# M2male_M2female_miniDP.net
KiCad netlist of a schematic drawn in Altium Designer
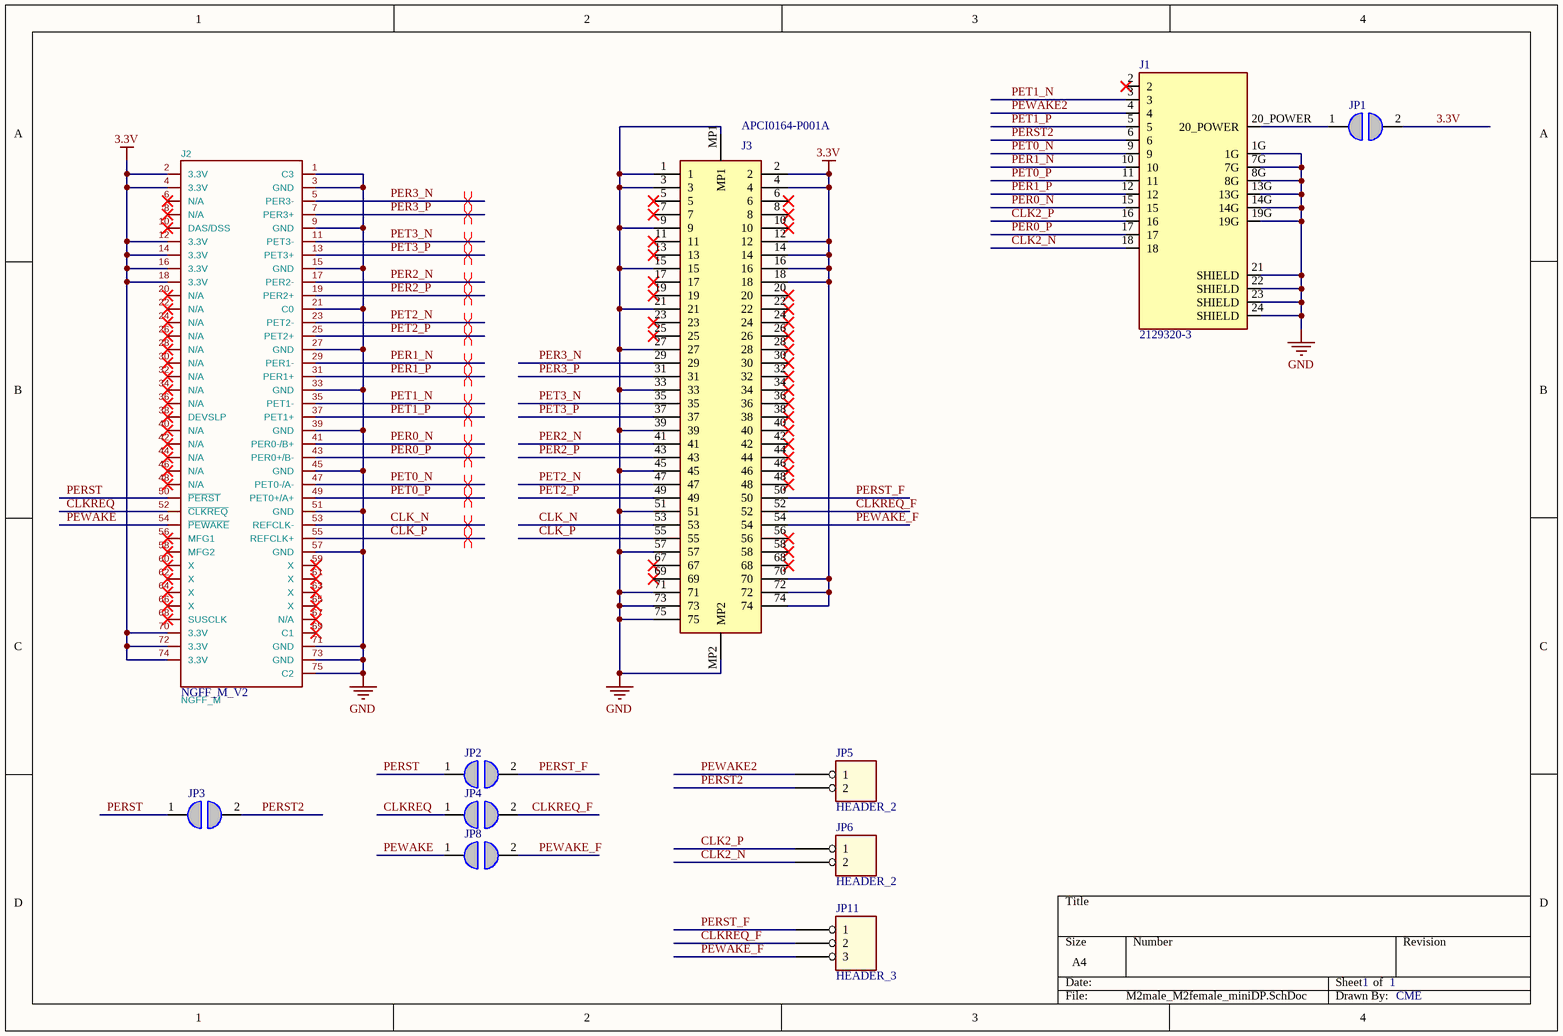
[diagram p0: M2male_M2female_miniDP.SchDoc]

(export (version "E")
  (design (tool "Eeschema 10.0.6"))
  (components
    (comp (ref "J1")
      (value "2129320-3")
      (footprint "CME_LIB:CONN_2129320-3")
      (description "Conn Display Port RCP 20 POS 0.9mm/1.8mm Solder RA Thru-Hole 20 Terminal 1 Port T/R")
      (fields (field (name "DIGI-KEY_PART_NUMBER") "A120537CT-ND") (field (name "MF") "TE Connectivity"))
      (libsource (lib "CME_LIB") (part "2129320-3"))
    )
    (comp (ref "J2")
      (value "NGFF_M_V2")
      (footprint "M2male_M2female_miniDP:M.2-M-KEY-2280-V2")
      (fields (field (name "ALTIUM_VALUE") "NGFF_M"))
      (libsource (lib "M2male_M2female_miniDP") (part "NGFF_M_V2"))
    )
    (comp (ref "J3")
      (value "APCI0164-P001A")
      (footprint "CME_LIB:APCI0164P001A")
      (description "Connector")
      (libsource (lib "*") (part "APCI0164-P001A"))
    )
    (comp (ref "JP1")
      (value "JUMPER_A_SOUDER")
      (footprint "JUMPER_A_SOUDER (0201)")
      (description "Pont à souder sur print")
      (libsource (lib "DatabaseReDS") (part "JUMPER_A_SOUDER"))
    )
    (comp (ref "JP2")
      (value "JUMPER_A_SOUDER")
      (footprint "JUMPER_A_SOUDER (0201)")
      (description "Pont à souder sur print")
      (libsource (lib "DatabaseReDS") (part "JUMPER_A_SOUDER"))
    )
    (comp (ref "JP3")
      (value "JUMPER_A_SOUDER")
      (footprint "JUMPER_A_SOUDER (0201)")
      (description "Pont à souder sur print")
      (libsource (lib "DatabaseReDS") (part "JUMPER_A_SOUDER"))
    )
    (comp (ref "JP4")
      (value "JUMPER_A_SOUDER")
      (footprint "JUMPER_A_SOUDER (0201)")
      (description "Pont à souder sur print")
      (libsource (lib "DatabaseReDS") (part "JUMPER_A_SOUDER"))
    )
    (comp (ref "JP5")
      (value "HEADER_2")
      (footprint "BLKCON.100/VH/TM1SQ/W.100/2")
      (description "Barrette simple 2 poles 2.54mm")
      (fields (field (name "MANUFACTURER") "TE Connectivity"))
      (libsource (lib "DatabaseReDS") (part "HEADER_2"))
    )
    (comp (ref "JP6")
      (value "HEADER_2")
      (footprint "BLKCON.100/VH/TM1SQ/W.100/2")
      (description "Barrette simple 2 poles 2.54mm")
      (fields (field (name "MANUFACTURER") "TE Connectivity"))
      (libsource (lib "DatabaseReDS") (part "HEADER_2"))
    )
    (comp (ref "JP8")
      (value "JUMPER_A_SOUDER")
      (footprint "JUMPER_A_SOUDER (0201)")
      (description "Pont à souder sur print")
      (libsource (lib "DatabaseReDS") (part "JUMPER_A_SOUDER"))
    )
    (comp (ref "JP11")
      (value "HEADER_3")
      (footprint "BLKCON.100/VH/TM1SQ/W.100/3")
      (description "Barrette simple 3 poles 2.54mm")
      (fields (field (name "MANUFACTURER") "TE Connectivity"))
      (libsource (lib "DatabaseReDS") (part "HEADER_3"))
    )
  )
  (nets
    (net (code "1") (name "/CLK2_N") (class "Default")
      (node (ref "J1") (pin "18") (pinfunction "18_18") (pintype "passive"))
      (node (ref "JP6") (pin "2") (pinfunction "2_2") (pintype "passive"))
    )
    (net (code "2") (name "/CLK2_P") (class "Default")
      (node (ref "J1") (pin "16") (pinfunction "16_16") (pintype "passive"))
      (node (ref "JP6") (pin "1") (pinfunction "1_1") (pintype "passive"))
    )
    (net (code "3") (name "/CLKREQ") (class "Default")
      (node (ref "J2") (pin "52") (pinfunction "~{CLKREQ}_52") (pintype "passive"))
      (node (ref "JP4") (pin "1") (pinfunction "1_1") (pintype "passive"))
    )
    (net (code "4") (name "/CLKREQ_F") (class "Default")
      (node (ref "J3") (pin "52") (pinfunction "52_52") (pintype "passive"))
      (node (ref "JP11") (pin "2") (pinfunction "2_2") (pintype "passive"))
      (node (ref "JP4") (pin "2") (pinfunction "2_2") (pintype "passive"))
    )
    (net (code "5") (name "/CLK_N") (class "Default")
      (node (ref "J2") (pin "53") (pinfunction "REFCLK-_53") (pintype "passive"))
      (node (ref "J3") (pin "53") (pinfunction "53_53") (pintype "passive"))
    )
    (net (code "6") (name "/CLK_P") (class "Default")
      (node (ref "J2") (pin "55") (pinfunction "REFCLK+_55") (pintype "passive"))
      (node (ref "J3") (pin "55") (pinfunction "55_55") (pintype "passive"))
    )
    (net (code "7") (name "/PER0_N") (class "Default")
      (node (ref "J1") (pin "15") (pinfunction "15_15") (pintype "passive"))
      (node (ref "J2") (pin "41") (pinfunction "PER0-/B+_41") (pintype "passive"))
    )
    (net (code "8") (name "/PER0_P") (class "Default")
      (node (ref "J1") (pin "17") (pinfunction "17_17") (pintype "passive"))
      (node (ref "J2") (pin "43") (pinfunction "PER0+/B-_43") (pintype "passive"))
    )
    (net (code "9") (name "/PER1_N") (class "Default")
      (node (ref "J1") (pin "10") (pinfunction "10_10") (pintype "passive"))
      (node (ref "J2") (pin "29") (pinfunction "PER1-_29") (pintype "passive"))
    )
    (net (code "10") (name "/PER1_P") (class "Default")
      (node (ref "J1") (pin "12") (pinfunction "12_12") (pintype "passive"))
      (node (ref "J2") (pin "31") (pinfunction "PER1+_31") (pintype "passive"))
    )
    (net (code "11") (name "/PER2_N") (class "Default")
      (node (ref "J2") (pin "17") (pinfunction "PER2-_17") (pintype "passive"))
      (node (ref "J3") (pin "41") (pinfunction "41_41") (pintype "passive"))
    )
    (net (code "12") (name "/PER2_P") (class "Default")
      (node (ref "J2") (pin "19") (pinfunction "PER2+_19") (pintype "passive"))
      (node (ref "J3") (pin "43") (pinfunction "43_43") (pintype "passive"))
    )
    (net (code "13") (name "/PER3_N") (class "Default")
      (node (ref "J2") (pin "5") (pinfunction "PER3-_5") (pintype "passive"))
      (node (ref "J3") (pin "29") (pinfunction "29_29") (pintype "passive"))
    )
    (net (code "14") (name "/PER3_P") (class "Default")
      (node (ref "J2") (pin "7") (pinfunction "PER3+_7") (pintype "passive"))
      (node (ref "J3") (pin "31") (pinfunction "31_31") (pintype "passive"))
    )
    (net (code "15") (name "/PERST") (class "Default")
      (node (ref "J2") (pin "50") (pinfunction "~{PERST}_50") (pintype "passive"))
      (node (ref "JP2") (pin "1") (pinfunction "1_1") (pintype "passive"))
      (node (ref "JP3") (pin "1") (pinfunction "1_1") (pintype "passive"))
    )
    (net (code "16") (name "/PERST2") (class "Default")
      (node (ref "J1") (pin "6") (pinfunction "6_6") (pintype "passive"))
      (node (ref "JP3") (pin "2") (pinfunction "2_2") (pintype "passive"))
      (node (ref "JP5") (pin "2") (pinfunction "2_2") (pintype "passive"))
    )
    (net (code "17") (name "/PERST_F") (class "Default")
      (node (ref "J3") (pin "50") (pinfunction "50_50") (pintype "passive"))
      (node (ref "JP11") (pin "1") (pinfunction "1_1") (pintype "passive"))
      (node (ref "JP2") (pin "2") (pinfunction "2_2") (pintype "passive"))
    )
    (net (code "18") (name "/PET0_N") (class "Default")
      (node (ref "J1") (pin "9") (pinfunction "9_9") (pintype "passive"))
      (node (ref "J2") (pin "47") (pinfunction "PET0-/A-_47") (pintype "passive"))
    )
    (net (code "19") (name "/PET0_P") (class "Default")
      (node (ref "J1") (pin "11") (pinfunction "11_11") (pintype "passive"))
      (node (ref "J2") (pin "49") (pinfunction "PET0+/A+_49") (pintype "passive"))
    )
    (net (code "20") (name "/PET1_N") (class "Default")
      (node (ref "J1") (pin "3") (pinfunction "3_3") (pintype "passive"))
      (node (ref "J2") (pin "35") (pinfunction "PET1-_35") (pintype "passive"))
    )
    (net (code "21") (name "/PET1_P") (class "Default")
      (node (ref "J1") (pin "5") (pinfunction "5_5") (pintype "passive"))
      (node (ref "J2") (pin "37") (pinfunction "PET1+_37") (pintype "passive"))
    )
    (net (code "22") (name "/PET2_N") (class "Default")
      (node (ref "J2") (pin "23") (pinfunction "PET2-_23") (pintype "passive"))
      (node (ref "J3") (pin "47") (pinfunction "47_47") (pintype "passive"))
    )
    (net (code "23") (name "/PET2_P") (class "Default")
      (node (ref "J2") (pin "25") (pinfunction "PET2+_25") (pintype "passive"))
      (node (ref "J3") (pin "49") (pinfunction "49_49") (pintype "passive"))
    )
    (net (code "24") (name "/PET3_N") (class "Default")
      (node (ref "J2") (pin "11") (pinfunction "PET3-_11") (pintype "passive"))
      (node (ref "J3") (pin "35") (pinfunction "35_35") (pintype "passive"))
    )
    (net (code "25") (name "/PET3_P") (class "Default")
      (node (ref "J2") (pin "13") (pinfunction "PET3+_13") (pintype "passive"))
      (node (ref "J3") (pin "37") (pinfunction "37_37") (pintype "passive"))
    )
    (net (code "26") (name "/PEWAKE") (class "Default")
      (node (ref "J2") (pin "54") (pinfunction "~{PEWAKE}_54") (pintype "passive"))
      (node (ref "JP8") (pin "1") (pinfunction "1_1") (pintype "passive"))
    )
    (net (code "27") (name "/PEWAKE2") (class "Default")
      (node (ref "J1") (pin "4") (pinfunction "4_4") (pintype "passive"))
      (node (ref "JP5") (pin "1") (pinfunction "1_1") (pintype "passive"))
    )
    (net (code "28") (name "/PEWAKE_F") (class "Default")
      (node (ref "J3") (pin "54") (pinfunction "54_54") (pintype "passive"))
      (node (ref "JP11") (pin "3") (pinfunction "3_3") (pintype "passive"))
      (node (ref "JP8") (pin "2") (pinfunction "2_2") (pintype "passive"))
    )
    (net (code "29") (name "3.3V") (class "Default")
      (node (ref "J2") (pin "12") (pinfunction "3.3V_12") (pintype "passive"))
      (node (ref "J2") (pin "14") (pinfunction "3.3V_14") (pintype "passive"))
      (node (ref "J2") (pin "16") (pinfunction "3.3V_16") (pintype "passive"))
      (node (ref "J2") (pin "18") (pinfunction "3.3V_18") (pintype "passive"))
      (node (ref "J2") (pin "2") (pinfunction "3.3V_2") (pintype "passive"))
      (node (ref "J2") (pin "4") (pinfunction "3.3V_4") (pintype "passive"))
      (node (ref "J2") (pin "70") (pinfunction "3.3V_70") (pintype "passive"))
      (node (ref "J2") (pin "72") (pinfunction "3.3V_72") (pintype "passive"))
      (node (ref "J2") (pin "74") (pinfunction "3.3V_74") (pintype "passive"))
      (node (ref "J3") (pin "12") (pinfunction "12_12") (pintype "passive"))
      (node (ref "J3") (pin "14") (pinfunction "14_14") (pintype "passive"))
      (node (ref "J3") (pin "16") (pinfunction "16_16") (pintype "passive"))
      (node (ref "J3") (pin "18") (pinfunction "18_18") (pintype "passive"))
      (node (ref "J3") (pin "2") (pinfunction "2_2") (pintype "passive"))
      (node (ref "J3") (pin "4") (pinfunction "4_4") (pintype "passive"))
      (node (ref "J3") (pin "70") (pinfunction "70_70") (pintype "passive"))
      (node (ref "J3") (pin "72") (pinfunction "72_72") (pintype "passive"))
      (node (ref "J3") (pin "74") (pinfunction "74_74") (pintype "passive"))
      (node (ref "JP1") (pin "2") (pinfunction "2_2") (pintype "passive"))
    )
    (net (code "30") (name "GND") (class "Default")
      (node (ref "J1") (pin "13G") (pinfunction "13G_13G") (pintype "passive"))
      (node (ref "J1") (pin "14G") (pinfunction "14G_14G") (pintype "passive"))
      (node (ref "J1") (pin "19G") (pinfunction "19G_19G") (pintype "passive"))
      (node (ref "J1") (pin "1G") (pinfunction "1G_1G") (pintype "passive"))
      (node (ref "J1") (pin "21") (pinfunction "SHIELD_21") (pintype "passive"))
      (node (ref "J1") (pin "22") (pinfunction "SHIELD_22") (pintype "passive"))
      (node (ref "J1") (pin "23") (pinfunction "SHIELD_23") (pintype "passive"))
      (node (ref "J1") (pin "24") (pinfunction "SHIELD_24") (pintype "passive"))
      (node (ref "J1") (pin "7G") (pinfunction "7G_7G") (pintype "passive"))
      (node (ref "J1") (pin "8G") (pinfunction "8G_8G") (pintype "passive"))
      (node (ref "J2") (pin "1") (pinfunction "C3_1") (pintype "passive"))
      (node (ref "J2") (pin "15") (pinfunction "GND_15") (pintype "passive"))
      (node (ref "J2") (pin "21") (pinfunction "C0_21") (pintype "passive"))
      (node (ref "J2") (pin "27") (pinfunction "GND_27") (pintype "passive"))
      (node (ref "J2") (pin "3") (pinfunction "GND_3") (pintype "passive"))
      (node (ref "J2") (pin "33") (pinfunction "GND_33") (pintype "passive"))
      (node (ref "J2") (pin "39") (pinfunction "GND_39") (pintype "passive"))
      (node (ref "J2") (pin "45") (pinfunction "GND_45") (pintype "passive"))
      (node (ref "J2") (pin "51") (pinfunction "GND_51") (pintype "passive"))
      (node (ref "J2") (pin "57") (pinfunction "GND_57") (pintype "passive"))
      (node (ref "J2") (pin "71") (pinfunction "GND_71") (pintype "passive"))
      (node (ref "J2") (pin "73") (pinfunction "GND_73") (pintype "passive"))
      (node (ref "J2") (pin "75") (pinfunction "C2_75") (pintype "passive"))
      (node (ref "J2") (pin "9") (pinfunction "GND_9") (pintype "passive"))
      (node (ref "J3") (pin "1") (pinfunction "1_1") (pintype "passive"))
      (node (ref "J3") (pin "15") (pinfunction "15_15") (pintype "passive"))
      (node (ref "J3") (pin "21") (pinfunction "21_21") (pintype "passive"))
      (node (ref "J3") (pin "27") (pinfunction "27_27") (pintype "passive"))
      (node (ref "J3") (pin "3") (pinfunction "3_3") (pintype "passive"))
      (node (ref "J3") (pin "33") (pinfunction "33_33") (pintype "passive"))
      (node (ref "J3") (pin "39") (pinfunction "39_39") (pintype "passive"))
      (node (ref "J3") (pin "45") (pinfunction "45_45") (pintype "passive"))
      (node (ref "J3") (pin "51") (pinfunction "51_51") (pintype "passive"))
      (node (ref "J3") (pin "57") (pinfunction "57_57") (pintype "passive"))
      (node (ref "J3") (pin "71") (pinfunction "71_71") (pintype "passive"))
      (node (ref "J3") (pin "73") (pinfunction "73_73") (pintype "passive"))
      (node (ref "J3") (pin "75") (pinfunction "75_75") (pintype "passive"))
      (node (ref "J3") (pin "9") (pinfunction "9_9") (pintype "passive"))
      (node (ref "J3") (pin "MP1") (pinfunction "MP1_MP1") (pintype "passive"))
      (node (ref "J3") (pin "MP2") (pinfunction "MP2_MP2") (pintype "passive"))
    )
    (net (code "31") (name "Net-(J1-Pad20_POWER)") (class "Default")
      (node (ref "J1") (pin "20_POWER") (pinfunction "20_POWER_20_POWER") (pintype "passive"))
      (node (ref "JP1") (pin "1") (pinfunction "1_1") (pintype "passive"))
    )
    (net (code "32") (name "unconnected-(J1-Pad2)") (class "Default")
      (node (ref "J1") (pin "2") (pinfunction "2_2") (pintype "passive+no_connect"))
    )
    (net (code "33") (name "unconnected-(J2-C1-Pad69)") (class "Default")
      (node (ref "J2") (pin "69") (pinfunction "C1_69") (pintype "passive+no_connect"))
    )
    (net (code "34") (name "unconnected-(J2-DAS{slash}DSS-Pad10)") (class "Default")
      (node (ref "J2") (pin "10") (pinfunction "DAS/DSS_10") (pintype "passive+no_connect"))
    )
    (net (code "35") (name "unconnected-(J2-DEVSLP-Pad38)") (class "Default")
      (node (ref "J2") (pin "38") (pinfunction "DEVSLP_38") (pintype "passive+no_connect"))
    )
    (net (code "36") (name "unconnected-(J2-MFG1-Pad56)") (class "Default")
      (node (ref "J2") (pin "56") (pinfunction "MFG1_56") (pintype "passive+no_connect"))
    )
    (net (code "37") (name "unconnected-(J2-MFG2-Pad58)") (class "Default")
      (node (ref "J2") (pin "58") (pinfunction "MFG2_58") (pintype "passive+no_connect"))
    )
    (net (code "38") (name "unconnected-(J2-N{slash}A-Pad6)") (class "Default")
      (node (ref "J2") (pin "6") (pinfunction "N/A_6") (pintype "passive+no_connect"))
    )
    (net (code "39") (name "unconnected-(J2-N{slash}A-Pad8)") (class "Default")
      (node (ref "J2") (pin "8") (pinfunction "N/A_8") (pintype "passive+no_connect"))
    )
    (net (code "40") (name "unconnected-(J2-N{slash}A-Pad20)") (class "Default")
      (node (ref "J2") (pin "20") (pinfunction "N/A_20") (pintype "passive+no_connect"))
    )
    (net (code "41") (name "unconnected-(J2-N{slash}A-Pad22)") (class "Default")
      (node (ref "J2") (pin "22") (pinfunction "N/A_22") (pintype "passive+no_connect"))
    )
    (net (code "42") (name "unconnected-(J2-N{slash}A-Pad24)") (class "Default")
      (node (ref "J2") (pin "24") (pinfunction "N/A_24") (pintype "passive+no_connect"))
    )
    (net (code "43") (name "unconnected-(J2-N{slash}A-Pad26)") (class "Default")
      (node (ref "J2") (pin "26") (pinfunction "N/A_26") (pintype "passive+no_connect"))
    )
    (net (code "44") (name "unconnected-(J2-N{slash}A-Pad28)") (class "Default")
      (node (ref "J2") (pin "28") (pinfunction "N/A_28") (pintype "passive+no_connect"))
    )
    (net (code "45") (name "unconnected-(J2-N{slash}A-Pad30)") (class "Default")
      (node (ref "J2") (pin "30") (pinfunction "N/A_30") (pintype "passive+no_connect"))
    )
    (net (code "46") (name "unconnected-(J2-N{slash}A-Pad32)") (class "Default")
      (node (ref "J2") (pin "32") (pinfunction "N/A_32") (pintype "passive+no_connect"))
    )
    (net (code "47") (name "unconnected-(J2-N{slash}A-Pad34)") (class "Default")
      (node (ref "J2") (pin "34") (pinfunction "N/A_34") (pintype "passive+no_connect"))
    )
    (net (code "48") (name "unconnected-(J2-N{slash}A-Pad36)") (class "Default")
      (node (ref "J2") (pin "36") (pinfunction "N/A_36") (pintype "passive+no_connect"))
    )
    (net (code "49") (name "unconnected-(J2-N{slash}A-Pad40)") (class "Default")
      (node (ref "J2") (pin "40") (pinfunction "N/A_40") (pintype "passive+no_connect"))
    )
    (net (code "50") (name "unconnected-(J2-N{slash}A-Pad42)") (class "Default")
      (node (ref "J2") (pin "42") (pinfunction "N/A_42") (pintype "passive+no_connect"))
    )
    (net (code "51") (name "unconnected-(J2-N{slash}A-Pad44)") (class "Default")
      (node (ref "J2") (pin "44") (pinfunction "N/A_44") (pintype "passive+no_connect"))
    )
    (net (code "52") (name "unconnected-(J2-N{slash}A-Pad46)") (class "Default")
      (node (ref "J2") (pin "46") (pinfunction "N/A_46") (pintype "passive+no_connect"))
    )
    (net (code "53") (name "unconnected-(J2-N{slash}A-Pad48)") (class "Default")
      (node (ref "J2") (pin "48") (pinfunction "N/A_48") (pintype "passive+no_connect"))
    )
    (net (code "54") (name "unconnected-(J2-N{slash}A-Pad67)") (class "Default")
      (node (ref "J2") (pin "67") (pinfunction "N/A_67") (pintype "passive+no_connect"))
    )
    (net (code "55") (name "unconnected-(J2-SUSCLK-Pad68)") (class "Default")
      (node (ref "J2") (pin "68") (pinfunction "SUSCLK_68") (pintype "passive+no_connect"))
    )
    (net (code "56") (name "unconnected-(J2-X-Pad59)") (class "Default")
      (node (ref "J2") (pin "59") (pinfunction "X_59") (pintype "passive+no_connect"))
    )
    (net (code "57") (name "unconnected-(J2-X-Pad60)") (class "Default")
      (node (ref "J2") (pin "60") (pinfunction "X_60") (pintype "passive+no_connect"))
    )
    (net (code "58") (name "unconnected-(J2-X-Pad61)") (class "Default")
      (node (ref "J2") (pin "61") (pinfunction "X_61") (pintype "passive+no_connect"))
    )
    (net (code "59") (name "unconnected-(J2-X-Pad62)") (class "Default")
      (node (ref "J2") (pin "62") (pinfunction "X_62") (pintype "passive+no_connect"))
    )
    (net (code "60") (name "unconnected-(J2-X-Pad63)") (class "Default")
      (node (ref "J2") (pin "63") (pinfunction "X_63") (pintype "passive+no_connect"))
    )
    (net (code "61") (name "unconnected-(J2-X-Pad64)") (class "Default")
      (node (ref "J2") (pin "64") (pinfunction "X_64") (pintype "passive+no_connect"))
    )
    (net (code "62") (name "unconnected-(J2-X-Pad65)") (class "Default")
      (node (ref "J2") (pin "65") (pinfunction "X_65") (pintype "passive+no_connect"))
    )
    (net (code "63") (name "unconnected-(J2-X-Pad66)") (class "Default")
      (node (ref "J2") (pin "66") (pinfunction "X_66") (pintype "passive+no_connect"))
    )
    (net (code "64") (name "unconnected-(J3-Pad5)") (class "Default")
      (node (ref "J3") (pin "5") (pinfunction "5_5") (pintype "passive+no_connect"))
    )
    (net (code "65") (name "unconnected-(J3-Pad6)") (class "Default")
      (node (ref "J3") (pin "6") (pinfunction "6_6") (pintype "passive+no_connect"))
    )
    (net (code "66") (name "unconnected-(J3-Pad7)") (class "Default")
      (node (ref "J3") (pin "7") (pinfunction "7_7") (pintype "passive+no_connect"))
    )
    (net (code "67") (name "unconnected-(J3-Pad8)") (class "Default")
      (node (ref "J3") (pin "8") (pinfunction "8_8") (pintype "passive+no_connect"))
    )
    (net (code "68") (name "unconnected-(J3-Pad10)") (class "Default")
      (node (ref "J3") (pin "10") (pinfunction "10_10") (pintype "passive+no_connect"))
    )
    (net (code "69") (name "unconnected-(J3-Pad11)") (class "Default")
      (node (ref "J3") (pin "11") (pinfunction "11_11") (pintype "passive+no_connect"))
    )
    (net (code "70") (name "unconnected-(J3-Pad13)") (class "Default")
      (node (ref "J3") (pin "13") (pinfunction "13_13") (pintype "passive+no_connect"))
    )
    (net (code "71") (name "unconnected-(J3-Pad17)") (class "Default")
      (node (ref "J3") (pin "17") (pinfunction "17_17") (pintype "passive+no_connect"))
    )
    (net (code "72") (name "unconnected-(J3-Pad19)") (class "Default")
      (node (ref "J3") (pin "19") (pinfunction "19_19") (pintype "passive+no_connect"))
    )
    (net (code "73") (name "unconnected-(J3-Pad20)") (class "Default")
      (node (ref "J3") (pin "20") (pinfunction "20_20") (pintype "passive+no_connect"))
    )
    (net (code "74") (name "unconnected-(J3-Pad22)") (class "Default")
      (node (ref "J3") (pin "22") (pinfunction "22_22") (pintype "passive+no_connect"))
    )
    (net (code "75") (name "unconnected-(J3-Pad23)") (class "Default")
      (node (ref "J3") (pin "23") (pinfunction "23_23") (pintype "passive+no_connect"))
    )
    (net (code "76") (name "unconnected-(J3-Pad24)") (class "Default")
      (node (ref "J3") (pin "24") (pinfunction "24_24") (pintype "passive+no_connect"))
    )
    (net (code "77") (name "unconnected-(J3-Pad25)") (class "Default")
      (node (ref "J3") (pin "25") (pinfunction "25_25") (pintype "passive+no_connect"))
    )
    (net (code "78") (name "unconnected-(J3-Pad26)") (class "Default")
      (node (ref "J3") (pin "26") (pinfunction "26_26") (pintype "passive+no_connect"))
    )
    (net (code "79") (name "unconnected-(J3-Pad28)") (class "Default")
      (node (ref "J3") (pin "28") (pinfunction "28_28") (pintype "passive+no_connect"))
    )
    (net (code "80") (name "unconnected-(J3-Pad30)") (class "Default")
      (node (ref "J3") (pin "30") (pinfunction "30_30") (pintype "passive+no_connect"))
    )
    (net (code "81") (name "unconnected-(J3-Pad32)") (class "Default")
      (node (ref "J3") (pin "32") (pinfunction "32_32") (pintype "passive+no_connect"))
    )
    (net (code "82") (name "unconnected-(J3-Pad34)") (class "Default")
      (node (ref "J3") (pin "34") (pinfunction "34_34") (pintype "passive+no_connect"))
    )
    (net (code "83") (name "unconnected-(J3-Pad36)") (class "Default")
      (node (ref "J3") (pin "36") (pinfunction "36_36") (pintype "passive+no_connect"))
    )
    (net (code "84") (name "unconnected-(J3-Pad38)") (class "Default")
      (node (ref "J3") (pin "38") (pinfunction "38_38") (pintype "passive+no_connect"))
    )
    (net (code "85") (name "unconnected-(J3-Pad40)") (class "Default")
      (node (ref "J3") (pin "40") (pinfunction "40_40") (pintype "passive+no_connect"))
    )
    (net (code "86") (name "unconnected-(J3-Pad42)") (class "Default")
      (node (ref "J3") (pin "42") (pinfunction "42_42") (pintype "passive+no_connect"))
    )
    (net (code "87") (name "unconnected-(J3-Pad44)") (class "Default")
      (node (ref "J3") (pin "44") (pinfunction "44_44") (pintype "passive+no_connect"))
    )
    (net (code "88") (name "unconnected-(J3-Pad46)") (class "Default")
      (node (ref "J3") (pin "46") (pinfunction "46_46") (pintype "passive+no_connect"))
    )
    (net (code "89") (name "unconnected-(J3-Pad48)") (class "Default")
      (node (ref "J3") (pin "48") (pinfunction "48_48") (pintype "passive+no_connect"))
    )
    (net (code "90") (name "unconnected-(J3-Pad56)") (class "Default")
      (node (ref "J3") (pin "56") (pinfunction "56_56") (pintype "passive+no_connect"))
    )
    (net (code "91") (name "unconnected-(J3-Pad58)") (class "Default")
      (node (ref "J3") (pin "58") (pinfunction "58_58") (pintype "passive+no_connect"))
    )
    (net (code "92") (name "unconnected-(J3-Pad67)") (class "Default")
      (node (ref "J3") (pin "67") (pinfunction "67_67") (pintype "passive+no_connect"))
    )
    (net (code "93") (name "unconnected-(J3-Pad68)") (class "Default")
      (node (ref "J3") (pin "68") (pinfunction "68_68") (pintype "passive+no_connect"))
    )
    (net (code "94") (name "unconnected-(J3-Pad69)") (class "Default")
      (node (ref "J3") (pin "69") (pinfunction "69_69") (pintype "passive+no_connect"))
    )
  )
)
